# ATmega328PB_Xplained_Mini_Target.net
KiCad netlist of a schematic drawn in Altium Designer
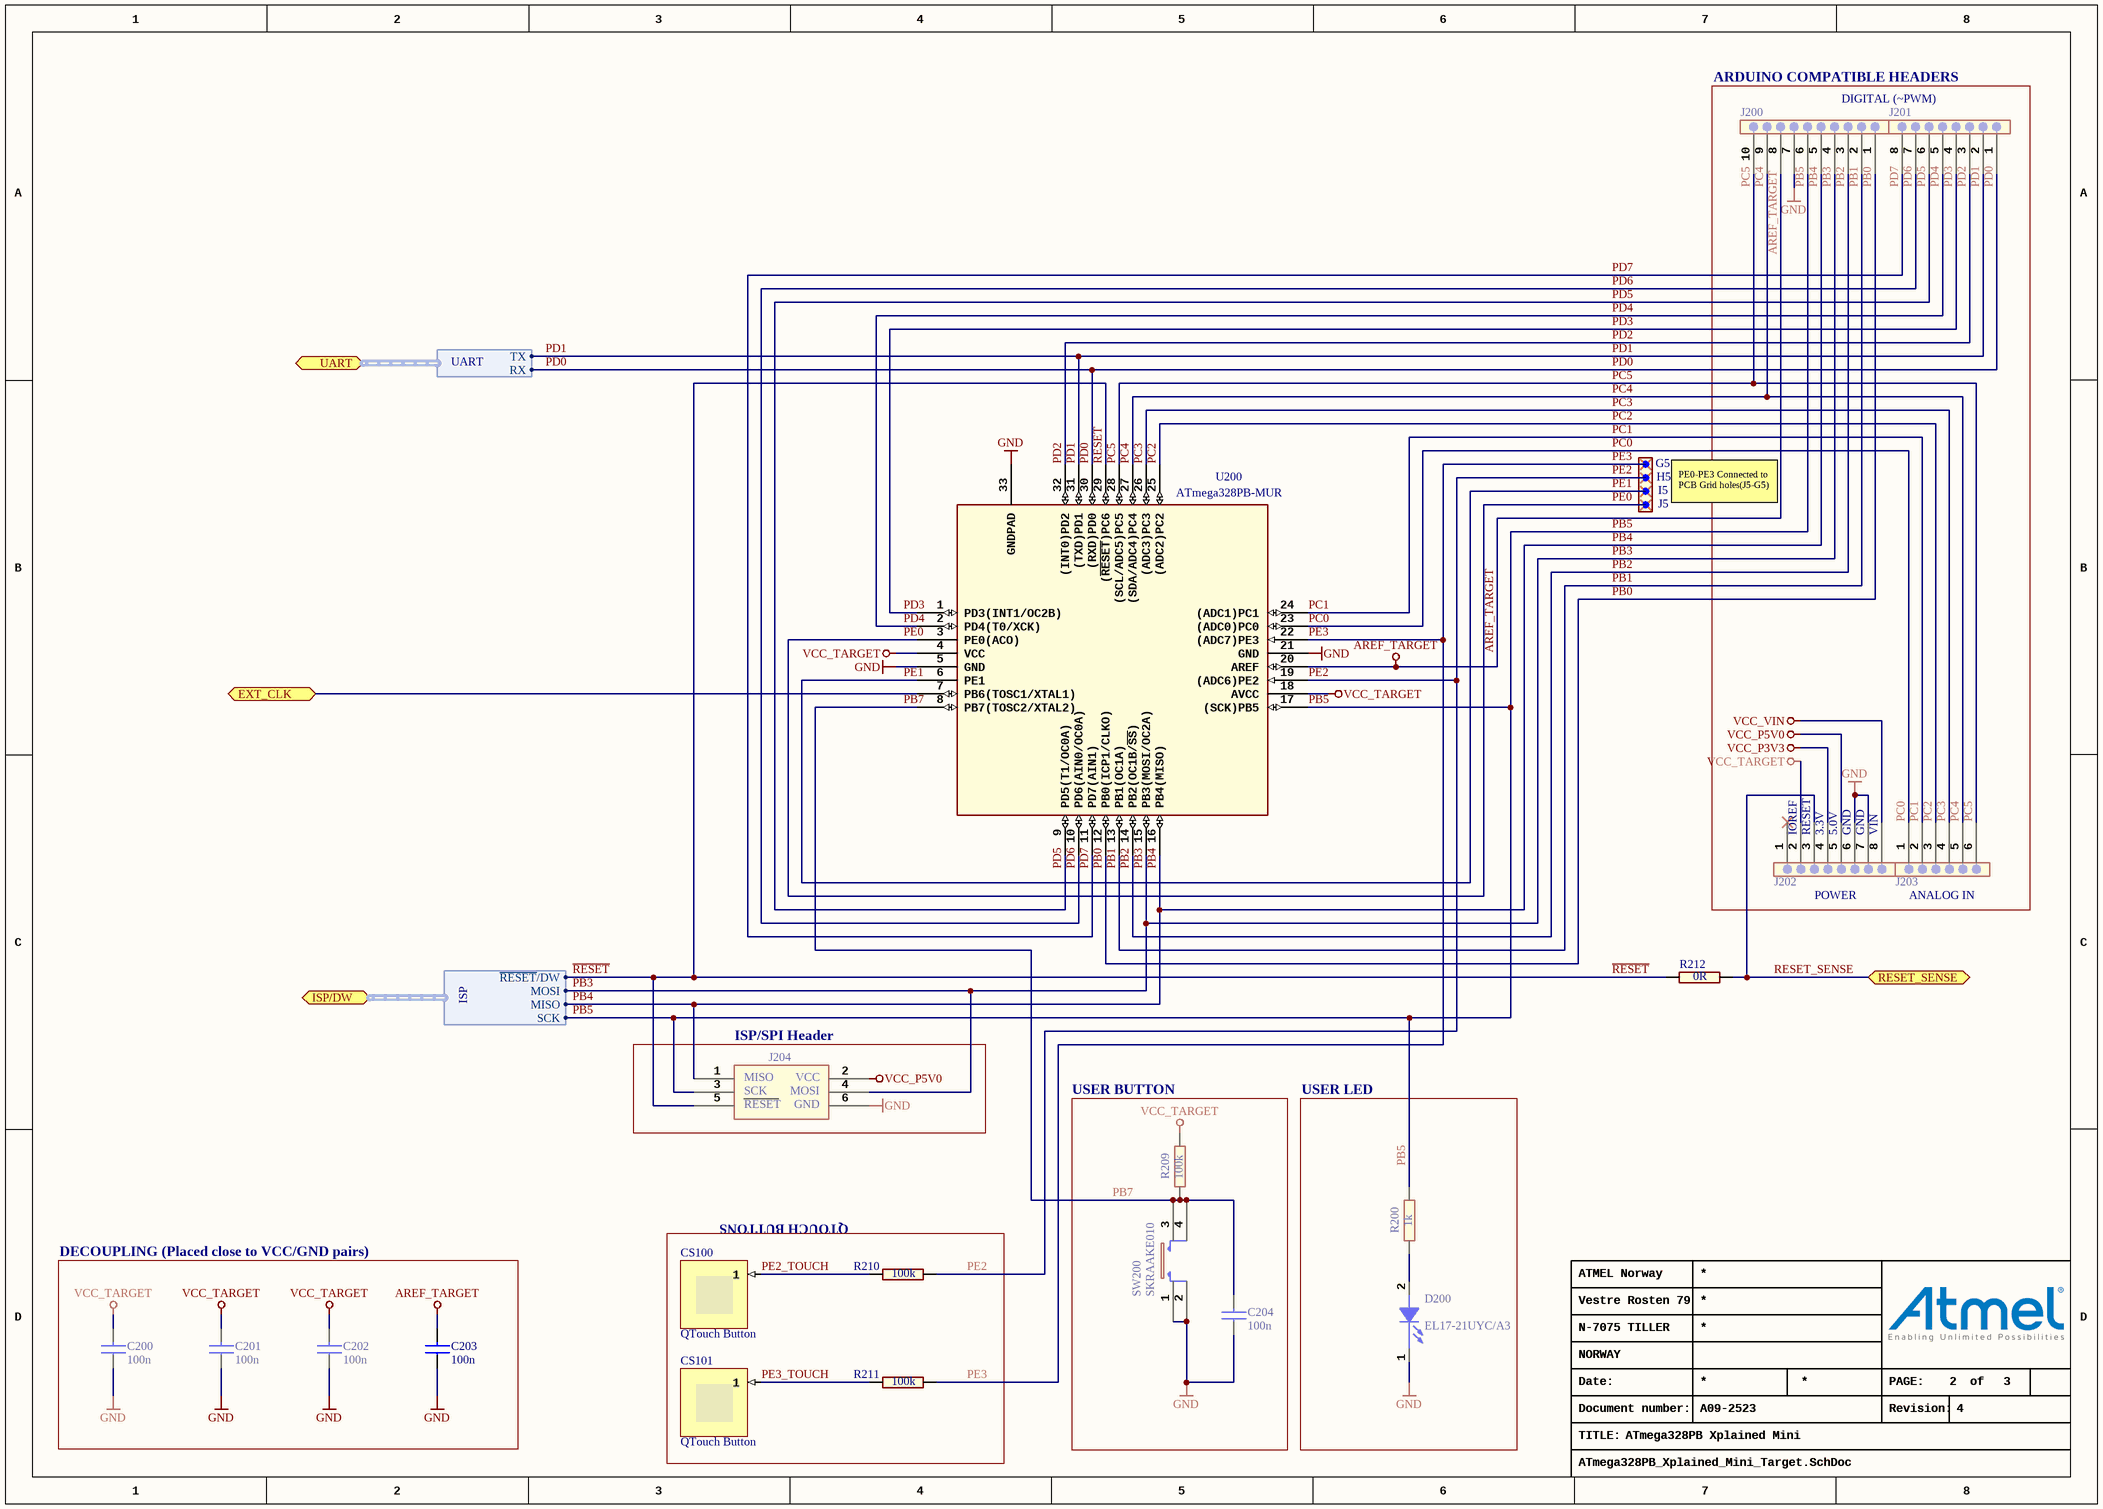
[diagram p0: ATmega328PB_Xplained_Mini_Target.SchDoc]

(export (version "E")
  (design (tool "Eeschema 10.0.6"))
  (components
    (comp (ref "C200")
      (value "100n")
      (footprint "AP1-00001")
      (description "Ceramic capacitor, SMD 0402, X7R, 16V, +/-10%")
      (fields (field (name "TOLERANCE") "16V, +/-10%") (field (name "MANUFACTURER") "Kemet"))
      (libsource (lib "AltiumDbLib") (part "CAP-NONPOL"))
    )
    (comp (ref "C201")
      (value "100n")
      (footprint "AP1-00001")
      (description "Ceramic capacitor, SMD 0402, X7R, 16V, +/-10%")
      (fields (field (name "TOLERANCE") "16V, +/-10%") (field (name "MANUFACTURER") "Kemet"))
      (libsource (lib "AltiumDbLib") (part "CAP-NONPOL"))
    )
    (comp (ref "C202")
      (value "100n")
      (footprint "AP1-00001")
      (description "Ceramic capacitor, SMD 0402, X7R, 16V, +/-10%")
      (fields (field (name "TOLERANCE") "16V, +/-10%") (field (name "MANUFACTURER") "Kemet"))
      (libsource (lib "AltiumDbLib") (part "CAP-NONPOL"))
    )
    (comp (ref "C203")
      (value "100n")
      (footprint "AP1-00001")
      (description "Ceramic capacitor, SMD 0402, X7R, 16V, +/-10%")
      (fields (field (name "TOLERANCE") "16V, +/-10%") (field (name "MANUFACTURER") "Kemet"))
      (libsource (lib "AltiumDbLib") (part "CAP-NONPOL"))
    )
    (comp (ref "C204")
      (value "100n")
      (footprint "AP1-00001")
      (description "Ceramic capacitor, SMD 0402, X7R, 16V, +/-10%")
      (fields (field (name "TOLERANCE") "16V, +/-10%") (field (name "MANUFACTURER") "Kemet"))
      (libsource (lib "AltiumDbLib") (part "CAP-NONPOL"))
    )
    (comp (ref "CS100") (value "QTouch Button") (libsource (lib "Atmel QTouch") (part "QTouchButton")))
    (comp (ref "CS101") (value "QTouch Button") (libsource (lib "Atmel QTouch") (part "QTouchButton")))
    (comp (ref "D200")
      (value "EL17-21UYC/A3")
      (footprint "AP4-00013")
      (description "LED, Yellow, Wave length=591nm, SMD 0805, ±70°")
      (fields (field (name "MANUFACTURER") "Everlight") (field (name "MPN") "17-21UYC/S530-A3/TR8"))
      (libsource (lib "AltiumDbLib") (part "LED_12"))
    )
    (comp (ref "J200")
      (value "~")
      (footprint "AP8-00822")
      (description "1x10 receptacle pin header, low insertion force, 2.54mm pitch THM, Pin in Paste")
      (fields (field (name "MANUFACTURER") "SAMTEC") (field (name "MPN") "SSQ-110-21-F-S"))
      (libsource (lib "AltiumDbLib") (part "HEADER 1x10 FEMALE"))
    )
    (comp (ref "J201")
      (value "~")
      (footprint "AP8-00823")
      (description "1x8 receptacle pin header, low insertion force, 2.54mm pitch THM, Pin in Paste")
      (fields (field (name "MANUFACTURER") "SAMTEC") (field (name "MPN") "SSQ-108-21-F-S"))
      (libsource (lib "AltiumDbLib") (part "HEADER 1x8 FEMALE"))
    )
    (comp (ref "J202")
      (value "~")
      (footprint "AP8-00823")
      (description "1x8 receptacle pin header, low insertion force, 2.54mm pitch THM, Pin in Paste")
      (fields (field (name "MANUFACTURER") "SAMTEC") (field (name "MPN") "SSQ-108-21-F-S"))
      (libsource (lib "") (part "HEADER 1x8 FEMALE_1"))
    )
    (comp (ref "J203")
      (value "~")
      (footprint "AP8-00824")
      (description "1x6 receptacle pin header, low insertion force, 2.54mm pitch THM")
      (fields (field (name "MANUFACTURER") "SAMTEC") (field (name "MPN") "SSQ-106-21-F-S"))
      (libsource (lib "AltiumDbLib") (part "HEADER 1x6 FEMALE"))
    )
    (comp (ref "J204")
      (value "~")
      (footprint "AP8-00182")
      (description "2x3 pin header, 2.54 mm pitch, THM")
      (fields (field (name "MANUFACTURER") "SAMTEC") (field (name "MPN") "MTSW-103-08-L-D-276"))
      (libsource (lib "AltiumDbLib") (part "HEADER 2x3"))
    )
    (comp (ref "R200")
      (value "1k")
      (footprint "AP2-00000")
      (description "Thick film resistor, SMD 0402, 1/16W, 1%")
      (fields (field (name "TOLERANCE") "1 %") (field (name "MANUFACTURER") "ASJ"))
      (libsource (lib "") (part "R2_1"))
    )
    (comp (ref "R209")
      (value "100k")
      (footprint "AP2-00000")
      (description "Thick film resistor, SMD 0402, 1/16W, 1%")
      (fields (field (name "TOLERANCE") "1 %") (field (name "MANUFACTURER") "ASJ"))
      (libsource (lib "") (part "R2_1"))
    )
    (comp (ref "R210")
      (value "100k")
      (footprint "AP2-00000")
      (description "Thick film resistor, SMD 0402, 1/16W, 1%")
      (fields (field (name "TOLERANCE") "1 %") (field (name "MANUFACTURER") "ASJ"))
      (libsource (lib "AltiumDbLib") (part "R2"))
    )
    (comp (ref "R211")
      (value "100k")
      (footprint "AP2-00000")
      (description "Thick film resistor, SMD 0402, 1/16W, 1%")
      (fields (field (name "TOLERANCE") "1 %") (field (name "MANUFACTURER") "ASJ"))
      (libsource (lib "AltiumDbLib") (part "R2"))
    )
    (comp (ref "R212")
      (value "0R")
      (footprint "AP2-00000")
      (description "RES 0.0 OHM 1/16W 0402 SMD")
      (fields (field (name "TOLERANCE") "1 %") (field (name "MANUFACTURER") "(n/a)"))
      (libsource (lib "AltiumDbLib") (part "R2"))
    )
    (comp (ref "SW200")
      (value "SKRAAKE010")
      (footprint "AP8-00137")
      (description "6.2x6.2 mm SMD tact switch, same as A08-0091 but less force is needed")
      (fields (field (name "MANUFACTURER") "ALPS"))
      (libsource (lib "AltiumDbLib") (part "PUSHBUTTON1"))
    )
    (comp (ref "U200")
      (value "ATmega328PB-MUR")
      (footprint "AP6-00155")
      (description "32k AVR with ADC/TWI/RS-232")
      (fields (field (name "MANUFACTURER") "ATMEL"))
      (libsource (lib "AltiumDbLib") (part "ATmega_48PB_88PB_168PB_328PB_32Pin_MLF"))
    )
  )
  (nets
    (net (code "3") (name "/EXT_CLK") (class "Default")
      (node (ref "U200") (pin "7") (pinfunction "PB6(TOSC1/XTAL1)_7") (pintype "bidirectional"))
    )
    (net (code "4") (name "/PB0") (class "Default")
      (node (ref "J200") (pin "1") (pinfunction "1_1") (pintype "passive"))
      (node (ref "U200") (pin "12") (pinfunction "PB0(ICP1/CLKO)_12") (pintype "bidirectional"))
    )
    (net (code "5") (name "/PB1") (class "Default")
      (node (ref "J200") (pin "2") (pinfunction "2_2") (pintype "passive"))
      (node (ref "U200") (pin "13") (pinfunction "PB1(OC1A)_13") (pintype "bidirectional"))
    )
    (net (code "6") (name "/PB2") (class "Default")
      (node (ref "J200") (pin "3") (pinfunction "3_3") (pintype "passive"))
      (node (ref "U200") (pin "14") (pinfunction "PB2(OC1B/~{SS})_14") (pintype "bidirectional"))
    )
    (net (code "7") (name "/PB3") (class "Default")
      (node (ref "J200") (pin "4") (pinfunction "4_4") (pintype "passive"))
      (node (ref "J204") (pin "4") (pinfunction "4_4") (pintype "passive"))
      (node (ref "U200") (pin "15") (pinfunction "PB3(MOSI/OC2A)_15") (pintype "bidirectional"))
    )
    (net (code "8") (name "/PB4") (class "Default")
      (node (ref "J200") (pin "5") (pinfunction "5_5") (pintype "passive"))
      (node (ref "J204") (pin "1") (pinfunction "1_1") (pintype "passive"))
      (node (ref "U200") (pin "16") (pinfunction "PB4(MISO)_16") (pintype "bidirectional"))
    )
    (net (code "9") (name "/PB5") (class "Default")
      (node (ref "J200") (pin "6") (pinfunction "6_6") (pintype "passive"))
      (node (ref "J204") (pin "3") (pinfunction "3_3") (pintype "passive"))
      (node (ref "R200") (pin "2") (pinfunction "2_2") (pintype "passive"))
      (node (ref "U200") (pin "17") (pinfunction "(SCK)PB5_17") (pintype "bidirectional"))
    )
    (net (code "10") (name "/PB7") (class "Default")
      (node (ref "C204") (pin "2") (pinfunction "2_2") (pintype "passive"))
      (node (ref "R209") (pin "1") (pinfunction "1_1") (pintype "passive"))
      (node (ref "SW200") (pin "3") (pinfunction "3_3") (pintype "passive"))
      (node (ref "SW200") (pin "4") (pinfunction "4_4") (pintype "passive"))
      (node (ref "U200") (pin "8") (pinfunction "PB7(TOSC2/XTAL2)_8") (pintype "bidirectional"))
    )
    (net (code "11") (name "/PC0") (class "Default")
      (node (ref "J203") (pin "1") (pinfunction "1_1") (pintype "passive"))
      (node (ref "U200") (pin "23") (pinfunction "(ADC0)PC0_23") (pintype "bidirectional"))
    )
    (net (code "12") (name "/PC1") (class "Default")
      (node (ref "J203") (pin "2") (pinfunction "2_2") (pintype "passive"))
      (node (ref "U200") (pin "24") (pinfunction "(ADC1)PC1_24") (pintype "bidirectional"))
    )
    (net (code "13") (name "/PC2") (class "Default")
      (node (ref "J203") (pin "3") (pinfunction "3_3") (pintype "passive"))
      (node (ref "U200") (pin "25") (pinfunction "(ADC2)PC2_25") (pintype "bidirectional"))
    )
    (net (code "14") (name "/PC3") (class "Default")
      (node (ref "J203") (pin "4") (pinfunction "4_4") (pintype "passive"))
      (node (ref "U200") (pin "26") (pinfunction "(ADC3)PC3_26") (pintype "bidirectional"))
    )
    (net (code "15") (name "/PC4") (class "Default")
      (node (ref "J200") (pin "9") (pinfunction "9_9") (pintype "passive"))
      (node (ref "J203") (pin "5") (pinfunction "5_5") (pintype "passive"))
      (node (ref "U200") (pin "27") (pinfunction "(SDA/ADC4)PC4_27") (pintype "bidirectional"))
    )
    (net (code "16") (name "/PC5") (class "Default")
      (node (ref "J200") (pin "10") (pinfunction "10_10") (pintype "passive"))
      (node (ref "J203") (pin "6") (pinfunction "6_6") (pintype "passive"))
      (node (ref "U200") (pin "28") (pinfunction "(SCL/ADC5)PC5_28") (pintype "bidirectional"))
    )
    (net (code "17") (name "/PD0") (class "Default")
      (node (ref "J201") (pin "1") (pinfunction "1_1") (pintype "passive"))
      (node (ref "U200") (pin "30") (pinfunction "(RXD)PD0_30") (pintype "bidirectional"))
    )
    (net (code "18") (name "/PD1") (class "Default")
      (node (ref "J201") (pin "2") (pinfunction "2_2") (pintype "passive"))
      (node (ref "U200") (pin "31") (pinfunction "(TXD)PD1_31") (pintype "bidirectional"))
    )
    (net (code "19") (name "/PD2") (class "Default")
      (node (ref "J201") (pin "3") (pinfunction "3_3") (pintype "passive"))
      (node (ref "U200") (pin "32") (pinfunction "(INT0)PD2_32") (pintype "bidirectional"))
    )
    (net (code "20") (name "/PD3") (class "Default")
      (node (ref "J201") (pin "4") (pinfunction "4_4") (pintype "passive"))
      (node (ref "U200") (pin "1") (pinfunction "PD3(INT1/OC2B)_1") (pintype "bidirectional"))
    )
    (net (code "21") (name "/PD4") (class "Default")
      (node (ref "J201") (pin "5") (pinfunction "5_5") (pintype "passive"))
      (node (ref "U200") (pin "2") (pinfunction "PD4(T0/XCK)_2") (pintype "bidirectional"))
    )
    (net (code "22") (name "/PD5") (class "Default")
      (node (ref "J201") (pin "6") (pinfunction "6_6") (pintype "passive"))
      (node (ref "U200") (pin "9") (pinfunction "PD5(T1/OC0A)_9") (pintype "bidirectional"))
    )
    (net (code "23") (name "/PD6") (class "Default")
      (node (ref "J201") (pin "7") (pinfunction "7_7") (pintype "passive"))
      (node (ref "U200") (pin "10") (pinfunction "PD6(AIN0/OC0A)_10") (pintype "bidirectional"))
    )
    (net (code "24") (name "/PD7") (class "Default")
      (node (ref "J201") (pin "8") (pinfunction "8_8") (pintype "passive"))
      (node (ref "U200") (pin "11") (pinfunction "PD7(AIN1)_11") (pintype "bidirectional"))
    )
    (net (code "25") (name "/PE0") (class "Default")
      (node (ref "U200") (pin "3") (pinfunction "PE0(ACO)_3") (pintype "power_in+no_connect"))
    )
    (net (code "26") (name "/PE1") (class "Default")
      (node (ref "U200") (pin "6") (pinfunction "PE1_6") (pintype "power_in+no_connect"))
    )
    (net (code "27") (name "/PE2") (class "Default")
      (node (ref "R210") (pin "2") (pinfunction "2_2") (pintype "passive"))
      (node (ref "U200") (pin "19") (pinfunction "(ADC6)PE2_19") (pintype "input"))
    )
    (net (code "28") (name "/PE2_TOUCH") (class "Default")
      (node (ref "CS100") (pin "1") (pinfunction "1_1") (pintype "input"))
      (node (ref "R210") (pin "1") (pinfunction "1_1") (pintype "passive"))
    )
    (net (code "29") (name "/PE3") (class "Default")
      (node (ref "R211") (pin "2") (pinfunction "2_2") (pintype "passive"))
      (node (ref "U200") (pin "22") (pinfunction "(ADC7)PE3_22") (pintype "input"))
    )
    (net (code "30") (name "/PE3_TOUCH") (class "Default")
      (node (ref "CS101") (pin "1") (pinfunction "1_1") (pintype "input"))
      (node (ref "R211") (pin "1") (pinfunction "1_1") (pintype "passive"))
    )
    (net (code "31") (name "/RESET_SENSE") (class "Default")
      (node (ref "J202") (pin "3") (pinfunction "3_3") (pintype "passive"))
      (node (ref "R212") (pin "2") (pinfunction "2_2") (pintype "passive"))
    )
    (net (code "34") (name "/~{RESET}") (class "Default")
      (node (ref "J204") (pin "5") (pinfunction "5_5") (pintype "passive"))
      (node (ref "R212") (pin "1") (pinfunction "1_1") (pintype "passive"))
      (node (ref "U200") (pin "29") (pinfunction "(~{RESET})PC6_29") (pintype "bidirectional"))
    )
    (net (code "35") (name "AREF_TARGET") (class "Default")
      (node (ref "C203") (pin "2") (pinfunction "2_2") (pintype "passive"))
      (node (ref "J200") (pin "8") (pinfunction "8_8") (pintype "passive"))
      (node (ref "U200") (pin "20") (pinfunction "AREF_20") (pintype "bidirectional"))
    )
    (net (code "36") (name "GND") (class "Default")
      (node (ref "C200") (pin "1") (pinfunction "1_1") (pintype "passive"))
      (node (ref "C201") (pin "1") (pinfunction "1_1") (pintype "passive"))
      (node (ref "C202") (pin "1") (pinfunction "1_1") (pintype "passive"))
      (node (ref "C203") (pin "1") (pinfunction "1_1") (pintype "passive"))
      (node (ref "C204") (pin "1") (pinfunction "1_1") (pintype "passive"))
      (node (ref "D200") (pin "1") (pinfunction "CATHODE_1") (pintype "passive"))
      (node (ref "J200") (pin "7") (pinfunction "7_7") (pintype "passive"))
      (node (ref "J202") (pin "6") (pinfunction "6_6") (pintype "passive"))
      (node (ref "J202") (pin "7") (pinfunction "7_7") (pintype "passive"))
      (node (ref "J204") (pin "6") (pinfunction "6_6") (pintype "passive"))
      (node (ref "SW200") (pin "1") (pinfunction "1_1") (pintype "passive"))
      (node (ref "SW200") (pin "2") (pinfunction "2_2") (pintype "passive"))
      (node (ref "U200") (pin "21") (pinfunction "GND_21") (pintype "power_in"))
      (node (ref "U200") (pin "33") (pinfunction "GNDPAD_33") (pintype "passive"))
      (node (ref "U200") (pin "5") (pinfunction "GND_5") (pintype "power_in"))
    )
    (net (code "37") (name "Net-(D200-ANODE)") (class "Default")
      (node (ref "D200") (pin "2") (pinfunction "ANODE_2") (pintype "passive"))
      (node (ref "R200") (pin "1") (pinfunction "1_1") (pintype "passive"))
    )
    (net (code "38") (name "VCC_P3V3") (class "Default")
      (node (ref "J202") (pin "4") (pinfunction "4_4") (pintype "passive"))
    )
    (net (code "39") (name "VCC_P5V0") (class "Default")
      (node (ref "J202") (pin "5") (pinfunction "5_5") (pintype "passive"))
      (node (ref "J204") (pin "2") (pinfunction "2_2") (pintype "passive"))
    )
    (net (code "40") (name "VCC_TARGET") (class "Default")
      (node (ref "C200") (pin "2") (pinfunction "2_2") (pintype "passive"))
      (node (ref "C201") (pin "2") (pinfunction "2_2") (pintype "passive"))
      (node (ref "C202") (pin "2") (pinfunction "2_2") (pintype "passive"))
      (node (ref "J202") (pin "2") (pinfunction "2_2") (pintype "passive"))
      (node (ref "R209") (pin "2") (pinfunction "2_2") (pintype "passive"))
      (node (ref "U200") (pin "18") (pinfunction "AVCC_18") (pintype "power_in"))
      (node (ref "U200") (pin "4") (pinfunction "VCC_4") (pintype "power_in"))
    )
    (net (code "41") (name "VCC_VIN") (class "Default")
      (node (ref "J202") (pin "8") (pinfunction "8_8") (pintype "passive"))
    )
    (net (code "42") (name "unconnected-(J202-Pad1)") (class "Default")
      (node (ref "J202") (pin "1") (pinfunction "1_1") (pintype "passive+no_connect"))
    )
  )
)
